# Sheet1.net
KiCad netlist of a schematic drawn in Altium Designer
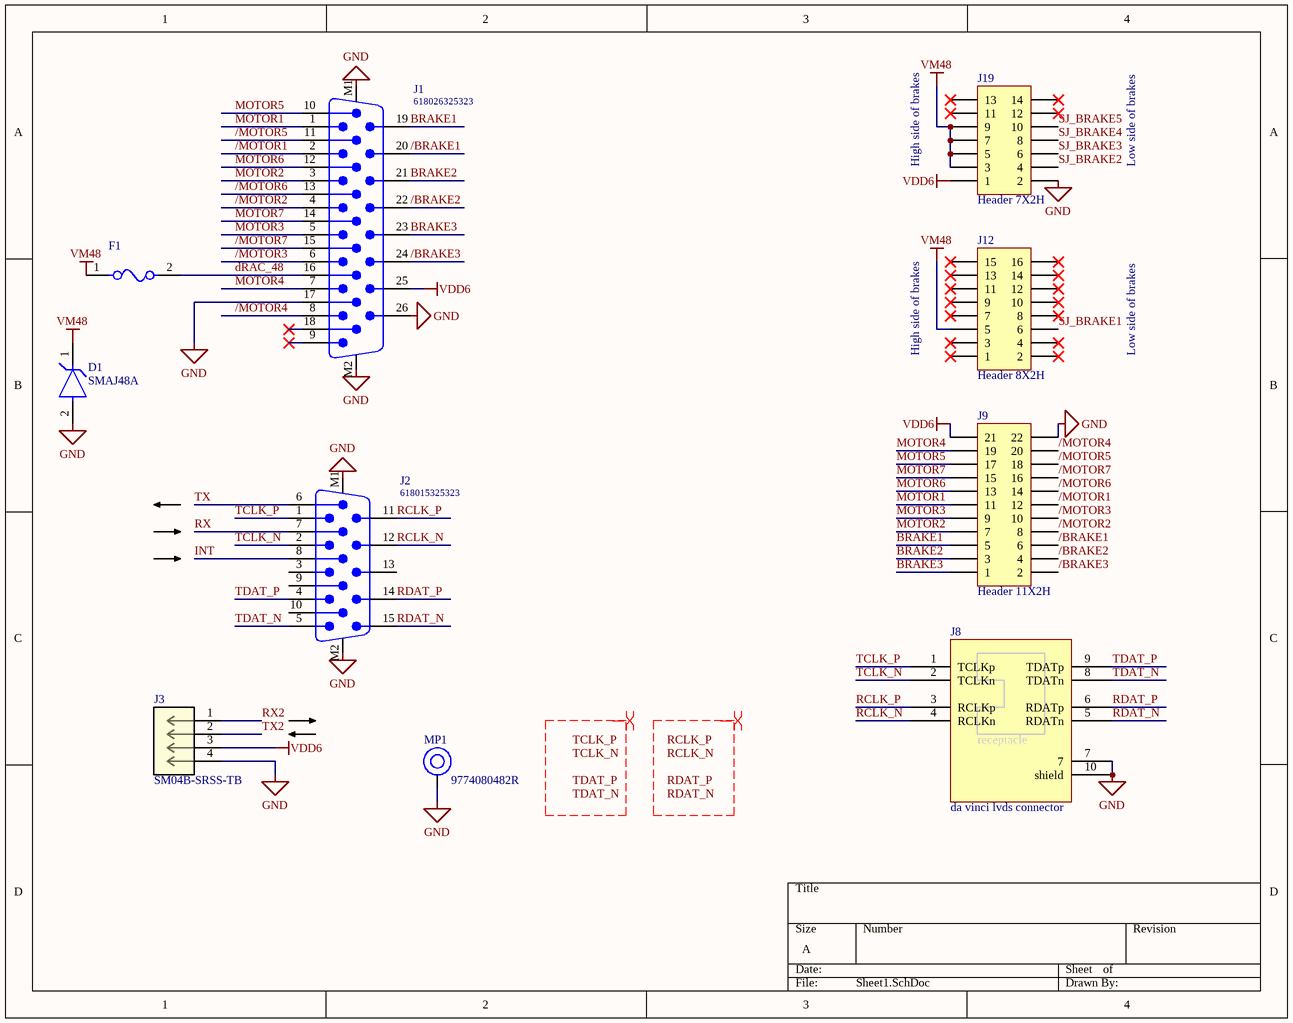
[diagram p0: Sheet1.SchDoc]

(export (version "E")
  (design (tool "Eeschema 10.0.6"))
  (components
    (comp (ref "D1")
      (value "SMAJ48A")
      (footprint "FP-SMAJ-MFG")
      (description "TVS DIODE 48V 77.4V SMA")
      (fields
        (field (name "MANUFACTURER") "Bourns Inc.")
        (field (name "OCTOPART") "https://octopart.com/smaj48a-bourns-12809387")
      )
      (libsource (lib "Altium Content Vault") (part "f813f71cba58e380607f5dd3caf9714"))
    )
    (comp (ref "F1")
      (value "0466003.NR")
      (footprint "FP-0466-MFG")
      (description "FUSE BOARD MNT 3A 32VAC/VDC 1206")
      (fields
        (field (name "OCTOPART") "https://octopart.com/0466003.nr-littelfuse-565175")
        (field (name "MANUFACTURER") "Littelfuse")
      )
      (libsource (lib "Altium Content Vault") (part "5bcf9b9f640e542cf0359d10258e979"))
    )
    (comp (ref "J1")
      (value "618026325323")
      (footprint "618026325323")
      (description "Male High Density PCB Connector without Hex Screw WR-DSUB, Angled, 26 pins")
      (fields (field (name "MANUFACTURER") "Wurth Elektronik") (field (name "PUBLISHER") "WurthElektronik"))
      (libsource (lib "Altium Content Vault") (part "WE-CN-3S-2M-D26"))
    )
    (comp (ref "J2")
      (value "618015325323")
      (footprint "618015325323")
      (description "Male High Density PCB Connector without Hex Screw WR-DSUB, Angled, 15 pins")
      (fields (field (name "MANUFACTURER") "Wurth Elektronik") (field (name "PUBLISHER") "WurthElektronik"))
      (libsource (lib "Altium Content Vault") (part "WE-CN-3S-2M-D15"))
    )
    (comp (ref "J3")
      (value "SM04B-SRSS-TB")
      (footprint "CONN_SM04B-SRSS-TB_JST")
      (description "No Description Available")
      (libsource (lib "SM04B-SRSS-TB") (part "SM04B-SRSS-TB"))
    )
    (comp (ref "J8")
      (value "da vinci lvds connector")
      (footprint "1394b")
      (libsource (lib "Schlib1") (part "davinci_lvds"))
    )
    (comp (ref "J9")
      (value "Header 11X2H")
      (footprint "jst_pad22")
      (description "Header, 11-Pin, Dual row, Right Angle")
      (fields (field (name "PUBLISHER") "Altium Limited"))
      (libsource (lib "Miscellaneous Connectors") (part "Header 11X2H"))
    )
    (comp (ref "J12")
      (value "Header 8X2H")
      (footprint "jst_pad16")
      (description "Header, 8-Pin, Dual row, Right Angle")
      (fields (field (name "PUBLISHER") "Altium Limited"))
      (libsource (lib "Miscellaneous Connectors") (part "Header 8X2H"))
    )
    (comp (ref "J19")
      (value "Header 7X2H")
      (footprint "jst_pad14")
      (description "Header, 7-Pin, Dual row, Right Angle")
      (fields (field (name "PUBLISHER") "Altium Limited"))
      (libsource (lib "Miscellaneous Connectors") (part "Header 7X2H"))
    )
    (comp (ref "MP1")
      (value "9774080482R")
      (footprint "9774080482")
      (description "9774080482R WA-SMSI SMT Steel Spacer, M4 Internal non Stop")
      (libsource (lib "Altium Content Vault") (part "Spacer"))
    )
  )
  (nets
    (net (code "1") (name "/BRAKE1") (class "Default")
      (node (ref "J1") (pin "19") (pinfunction "19_19") (pintype "passive"))
      (node (ref "J9") (pin "5") (pinfunction "5_5") (pintype "passive"))
    )
    (net (code "2") (name "/BRAKE2") (class "Default")
      (node (ref "J1") (pin "21") (pinfunction "21_21") (pintype "passive"))
      (node (ref "J9") (pin "3") (pinfunction "3_3") (pintype "passive"))
    )
    (net (code "3") (name "/BRAKE3") (class "Default")
      (node (ref "J1") (pin "23") (pinfunction "23_23") (pintype "passive"))
      (node (ref "J9") (pin "1") (pinfunction "1_1") (pintype "passive"))
    )
    (net (code "4") (name "/INT") (class "Default")
      (node (ref "J2") (pin "8") (pinfunction "8_8") (pintype "passive"))
    )
    (net (code "5") (name "/MOTOR1") (class "Default")
      (node (ref "J1") (pin "1") (pinfunction "1_1") (pintype "passive"))
      (node (ref "J9") (pin "11") (pinfunction "11_11") (pintype "passive"))
    )
    (net (code "6") (name "/MOTOR2") (class "Default")
      (node (ref "J1") (pin "3") (pinfunction "3_3") (pintype "passive"))
      (node (ref "J9") (pin "7") (pinfunction "7_7") (pintype "passive"))
    )
    (net (code "7") (name "/MOTOR3") (class "Default")
      (node (ref "J1") (pin "5") (pinfunction "5_5") (pintype "passive"))
      (node (ref "J9") (pin "9") (pinfunction "9_9") (pintype "passive"))
    )
    (net (code "8") (name "/MOTOR4") (class "Default")
      (node (ref "J1") (pin "7") (pinfunction "7_7") (pintype "passive"))
      (node (ref "J9") (pin "19") (pinfunction "19_19") (pintype "passive"))
    )
    (net (code "9") (name "/MOTOR5") (class "Default")
      (node (ref "J1") (pin "10") (pinfunction "10_10") (pintype "passive"))
      (node (ref "J9") (pin "17") (pinfunction "17_17") (pintype "passive"))
    )
    (net (code "10") (name "/MOTOR6") (class "Default")
      (node (ref "J1") (pin "12") (pinfunction "12_12") (pintype "passive"))
      (node (ref "J9") (pin "13") (pinfunction "13_13") (pintype "passive"))
    )
    (net (code "11") (name "/MOTOR7") (class "Default")
      (node (ref "J1") (pin "14") (pinfunction "14_14") (pintype "passive"))
      (node (ref "J9") (pin "15") (pinfunction "15_15") (pintype "passive"))
    )
    (net (code "12") (name "/RCLK_N") (class "Default")
      (node (ref "J2") (pin "12") (pinfunction "12_12") (pintype "passive"))
      (node (ref "J8") (pin "4") (pinfunction "RCLKn_4") (pintype "passive"))
    )
    (net (code "13") (name "/RCLK_P") (class "Default")
      (node (ref "J2") (pin "11") (pinfunction "11_11") (pintype "passive"))
      (node (ref "J8") (pin "3") (pinfunction "RCLKp_3") (pintype "passive"))
    )
    (net (code "14") (name "/RDAT_N") (class "Default")
      (node (ref "J2") (pin "15") (pinfunction "15_15") (pintype "passive"))
      (node (ref "J8") (pin "5") (pinfunction "RDATn_5") (pintype "passive"))
    )
    (net (code "15") (name "/RDAT_P") (class "Default")
      (node (ref "J2") (pin "14") (pinfunction "14_14") (pintype "passive"))
      (node (ref "J8") (pin "6") (pinfunction "RDATp_6") (pintype "passive"))
    )
    (net (code "16") (name "/RX") (class "Default")
      (node (ref "J2") (pin "7") (pinfunction "7_7") (pintype "passive"))
    )
    (net (code "17") (name "/RX2") (class "Default")
      (node (ref "J3") (pin "1") (pinfunction "1_1") (pintype "passive"))
    )
    (net (code "18") (name "/SJ_BRAKE1") (class "Default")
      (node (ref "J12") (pin "6") (pinfunction "6_6") (pintype "passive"))
    )
    (net (code "19") (name "/SJ_BRAKE2") (class "Default")
      (node (ref "J19") (pin "4") (pinfunction "4_4") (pintype "passive"))
    )
    (net (code "20") (name "/SJ_BRAKE3") (class "Default")
      (node (ref "J19") (pin "6") (pinfunction "6_6") (pintype "passive"))
    )
    (net (code "21") (name "/SJ_BRAKE4") (class "Default")
      (node (ref "J19") (pin "8") (pinfunction "8_8") (pintype "passive"))
    )
    (net (code "22") (name "/SJ_BRAKE5") (class "Default")
      (node (ref "J19") (pin "10") (pinfunction "10_10") (pintype "passive"))
    )
    (net (code "23") (name "/TCLK_N") (class "Default")
      (node (ref "J2") (pin "2") (pinfunction "2_2") (pintype "passive"))
      (node (ref "J8") (pin "2") (pinfunction "TCLKn_2") (pintype "passive"))
    )
    (net (code "24") (name "/TCLK_P") (class "Default")
      (node (ref "J2") (pin "1") (pinfunction "1_1") (pintype "passive"))
      (node (ref "J8") (pin "1") (pinfunction "TCLKp_1") (pintype "passive"))
    )
    (net (code "25") (name "/TDAT_N") (class "Default")
      (node (ref "J2") (pin "5") (pinfunction "5_5") (pintype "passive"))
      (node (ref "J8") (pin "8") (pinfunction "TDATn_8") (pintype "passive"))
    )
    (net (code "26") (name "/TDAT_P") (class "Default")
      (node (ref "J2") (pin "4") (pinfunction "4_4") (pintype "passive"))
      (node (ref "J8") (pin "9") (pinfunction "TDATp_9") (pintype "passive"))
    )
    (net (code "27") (name "/TX") (class "Default")
      (node (ref "J2") (pin "6") (pinfunction "6_6") (pintype "passive"))
    )
    (net (code "28") (name "/TX2") (class "Default")
      (node (ref "J3") (pin "2") (pinfunction "2_2") (pintype "passive"))
    )
    (net (code "29") (name "/dRAC_48") (class "Default")
      (node (ref "F1") (pin "2") (pinfunction "2_2") (pintype "passive"))
      (node (ref "J1") (pin "16") (pinfunction "16_16") (pintype "passive"))
    )
    (net (code "30") (name "/{slash}BRAKE1") (class "Default")
      (node (ref "J1") (pin "20") (pinfunction "20_20") (pintype "passive"))
      (node (ref "J9") (pin "6") (pinfunction "6_6") (pintype "passive"))
    )
    (net (code "31") (name "/{slash}BRAKE2") (class "Default")
      (node (ref "J1") (pin "22") (pinfunction "22_22") (pintype "passive"))
      (node (ref "J9") (pin "4") (pinfunction "4_4") (pintype "passive"))
    )
    (net (code "32") (name "/{slash}BRAKE3") (class "Default")
      (node (ref "J1") (pin "24") (pinfunction "24_24") (pintype "passive"))
      (node (ref "J9") (pin "2") (pinfunction "2_2") (pintype "passive"))
    )
    (net (code "33") (name "/{slash}MOTOR1") (class "Default")
      (node (ref "J1") (pin "2") (pinfunction "2_2") (pintype "passive"))
      (node (ref "J9") (pin "12") (pinfunction "12_12") (pintype "passive"))
    )
    (net (code "34") (name "/{slash}MOTOR2") (class "Default")
      (node (ref "J1") (pin "4") (pinfunction "4_4") (pintype "passive"))
      (node (ref "J9") (pin "8") (pinfunction "8_8") (pintype "passive"))
    )
    (net (code "35") (name "/{slash}MOTOR3") (class "Default")
      (node (ref "J1") (pin "6") (pinfunction "6_6") (pintype "passive"))
      (node (ref "J9") (pin "10") (pinfunction "10_10") (pintype "passive"))
    )
    (net (code "36") (name "/{slash}MOTOR4") (class "Default")
      (node (ref "J1") (pin "8") (pinfunction "8_8") (pintype "passive"))
      (node (ref "J9") (pin "20") (pinfunction "20_20") (pintype "passive"))
    )
    (net (code "37") (name "/{slash}MOTOR5") (class "Default")
      (node (ref "J1") (pin "11") (pinfunction "11_11") (pintype "passive"))
      (node (ref "J9") (pin "18") (pinfunction "18_18") (pintype "passive"))
    )
    (net (code "38") (name "/{slash}MOTOR6") (class "Default")
      (node (ref "J1") (pin "13") (pinfunction "13_13") (pintype "passive"))
      (node (ref "J9") (pin "14") (pinfunction "14_14") (pintype "passive"))
    )
    (net (code "39") (name "/{slash}MOTOR7") (class "Default")
      (node (ref "J1") (pin "15") (pinfunction "15_15") (pintype "passive"))
      (node (ref "J9") (pin "16") (pinfunction "16_16") (pintype "passive"))
    )
    (net (code "40") (name "GND") (class "Default")
      (node (ref "D1") (pin "2") (pinfunction "A_2") (pintype "passive"))
      (node (ref "J1") (pin "17") (pinfunction "17_17") (pintype "passive"))
      (node (ref "J1") (pin "26") (pinfunction "26_26") (pintype "passive"))
      (node (ref "J1") (pin "M1") (pinfunction "M1_M1") (pintype "passive"))
      (node (ref "J1") (pin "M2") (pinfunction "M2_M2") (pintype "passive"))
      (node (ref "J19") (pin "2") (pinfunction "2_2") (pintype "passive"))
      (node (ref "J2") (pin "M1") (pinfunction "M1_M1") (pintype "passive"))
      (node (ref "J2") (pin "M2") (pinfunction "M2_M2") (pintype "passive"))
      (node (ref "J3") (pin "4") (pinfunction "4_4") (pintype "passive"))
      (node (ref "J8") (pin "10") (pinfunction "shield_10") (pintype "passive"))
      (node (ref "J8") (pin "7") (pinfunction "7_7") (pintype "passive"))
      (node (ref "J9") (pin "22") (pinfunction "22_22") (pintype "passive"))
      (node (ref "MP1") (pin "1") (pinfunction "1_1") (pintype "passive"))
    )
    (net (code "41") (name "VDD6") (class "Default")
      (node (ref "J1") (pin "25") (pinfunction "25_25") (pintype "passive"))
      (node (ref "J19") (pin "1") (pinfunction "1_1") (pintype "passive"))
      (node (ref "J3") (pin "3") (pinfunction "3_3") (pintype "passive"))
      (node (ref "J9") (pin "21") (pinfunction "21_21") (pintype "passive"))
    )
    (net (code "42") (name "VM48") (class "Default")
      (node (ref "D1") (pin "1") (pinfunction "C_1") (pintype "passive"))
      (node (ref "F1") (pin "1") (pinfunction "1_1") (pintype "passive"))
      (node (ref "J12") (pin "5") (pinfunction "5_5") (pintype "passive"))
      (node (ref "J19") (pin "3") (pinfunction "3_3") (pintype "passive"))
      (node (ref "J19") (pin "5") (pinfunction "5_5") (pintype "passive"))
      (node (ref "J19") (pin "7") (pinfunction "7_7") (pintype "passive"))
      (node (ref "J19") (pin "9") (pinfunction "9_9") (pintype "passive"))
    )
    (net (code "43") (name "unconnected-(J1-Pad9)") (class "Default")
      (node (ref "J1") (pin "9") (pinfunction "9_9") (pintype "passive+no_connect"))
    )
    (net (code "44") (name "unconnected-(J1-Pad18)") (class "Default")
      (node (ref "J1") (pin "18") (pinfunction "18_18") (pintype "passive+no_connect"))
    )
    (net (code "45") (name "unconnected-(J2-Pad3)") (class "Default")
      (node (ref "J2") (pin "3") (pinfunction "3_3") (pintype "passive"))
    )
    (net (code "46") (name "unconnected-(J2-Pad9)") (class "Default")
      (node (ref "J2") (pin "9") (pinfunction "9_9") (pintype "passive"))
    )
    (net (code "47") (name "unconnected-(J2-Pad10)") (class "Default")
      (node (ref "J2") (pin "10") (pinfunction "10_10") (pintype "passive"))
    )
    (net (code "48") (name "unconnected-(J2-Pad13)") (class "Default")
      (node (ref "J2") (pin "13") (pinfunction "13_13") (pintype "passive"))
    )
    (net (code "49") (name "unconnected-(J12-Pad1)") (class "Default")
      (node (ref "J12") (pin "1") (pinfunction "1_1") (pintype "passive+no_connect"))
    )
    (net (code "50") (name "unconnected-(J12-Pad2)") (class "Default")
      (node (ref "J12") (pin "2") (pinfunction "2_2") (pintype "passive+no_connect"))
    )
    (net (code "51") (name "unconnected-(J12-Pad3)") (class "Default")
      (node (ref "J12") (pin "3") (pinfunction "3_3") (pintype "passive+no_connect"))
    )
    (net (code "52") (name "unconnected-(J12-Pad4)") (class "Default")
      (node (ref "J12") (pin "4") (pinfunction "4_4") (pintype "passive+no_connect"))
    )
    (net (code "53") (name "unconnected-(J12-Pad7)") (class "Default")
      (node (ref "J12") (pin "7") (pinfunction "7_7") (pintype "passive+no_connect"))
    )
    (net (code "54") (name "unconnected-(J12-Pad8)") (class "Default")
      (node (ref "J12") (pin "8") (pinfunction "8_8") (pintype "passive+no_connect"))
    )
    (net (code "55") (name "unconnected-(J12-Pad9)") (class "Default")
      (node (ref "J12") (pin "9") (pinfunction "9_9") (pintype "passive+no_connect"))
    )
    (net (code "56") (name "unconnected-(J12-Pad10)") (class "Default")
      (node (ref "J12") (pin "10") (pinfunction "10_10") (pintype "passive+no_connect"))
    )
    (net (code "57") (name "unconnected-(J12-Pad11)") (class "Default")
      (node (ref "J12") (pin "11") (pinfunction "11_11") (pintype "passive+no_connect"))
    )
    (net (code "58") (name "unconnected-(J12-Pad12)") (class "Default")
      (node (ref "J12") (pin "12") (pinfunction "12_12") (pintype "passive+no_connect"))
    )
    (net (code "59") (name "unconnected-(J12-Pad13)") (class "Default")
      (node (ref "J12") (pin "13") (pinfunction "13_13") (pintype "passive+no_connect"))
    )
    (net (code "60") (name "unconnected-(J12-Pad14)") (class "Default")
      (node (ref "J12") (pin "14") (pinfunction "14_14") (pintype "passive+no_connect"))
    )
    (net (code "61") (name "unconnected-(J12-Pad15)") (class "Default")
      (node (ref "J12") (pin "15") (pinfunction "15_15") (pintype "passive+no_connect"))
    )
    (net (code "62") (name "unconnected-(J12-Pad16)") (class "Default")
      (node (ref "J12") (pin "16") (pinfunction "16_16") (pintype "passive+no_connect"))
    )
    (net (code "63") (name "unconnected-(J19-Pad11)") (class "Default")
      (node (ref "J19") (pin "11") (pinfunction "11_11") (pintype "passive+no_connect"))
    )
    (net (code "64") (name "unconnected-(J19-Pad12)") (class "Default")
      (node (ref "J19") (pin "12") (pinfunction "12_12") (pintype "passive+no_connect"))
    )
    (net (code "65") (name "unconnected-(J19-Pad13)") (class "Default")
      (node (ref "J19") (pin "13") (pinfunction "13_13") (pintype "passive+no_connect"))
    )
    (net (code "66") (name "unconnected-(J19-Pad14)") (class "Default")
      (node (ref "J19") (pin "14") (pinfunction "14_14") (pintype "passive+no_connect"))
    )
  )
)
